# WIZARD_HV.net
KiCad netlist of a schematic drawn in Altium Designer
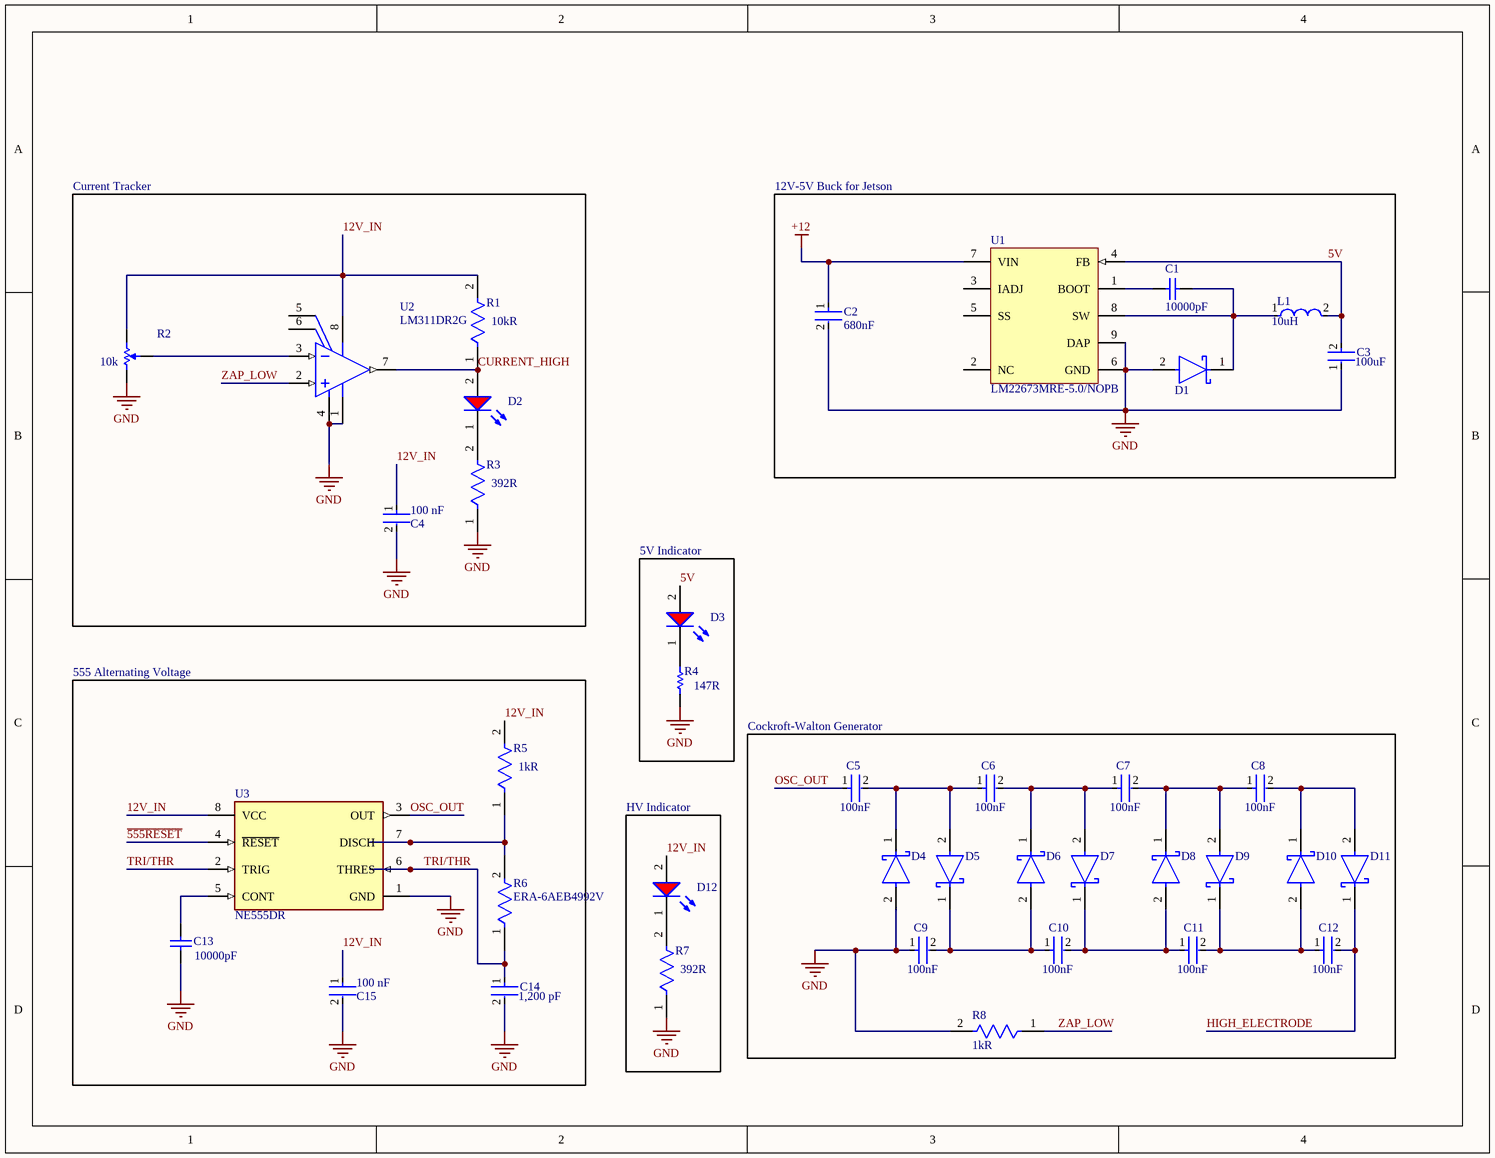
[diagram p0: WIZARD_HV.SchDoc]

(export (version "E")
  (design (tool "Eeschema 10.0.6"))
  (components
    (comp (ref "C1")
      (value "CL21B103KBANNNC")
      (footprint "CAPC2013X75X45LL10T25")
      (description "Multilayer Ceramic Capacitor, 10 nF, 50 V, -55 to 125 degC, 2-Pin SMD, RoHS, Tape and Reel")
      (fields
        (field (name "CAPACITANCE") "10000pF")
        (field (name "MANUFACTURER") "Samsung Electro-Mechanics")
      )
      (libsource (lib "Altium Content Vault") (part "CAP-NP-2"))
    )
    (comp (ref "C2")
      (value "CGA4J3X7R1E684K125AB")
      (footprint "FP-CGA4J-MFG")
      (description "Cap Ceramic 680nF 25V X7R 10% Pad SMD 0805 +125°C Automotive T/R")
      (fields (field (name "CAPACITANCE") "680nF") (field (name "TOLERANCE") "10%"))
      (libsource (lib "Altium Content Vault") (part "b4654b650e69147ec39a6b967a45e02"))
    )
    (comp (ref "C3")
      (value "GRM31CR61A107MEA8L")
      (footprint "FP-GRM31C-0_3-e0_3_0_8-IPC_B")
      (description "Chip Multilayer Ceramic Capacitors for General Purpose, 1206, 100uF, X5R, 15%, 20%, 10V")
      (fields (field (name "PARAMETER 1") "100uF"))
      (libsource (lib "Altium Content Vault") (part "f23184f103b6ebe33a8c269c53dcba6"))
    )
    (comp (ref "C4")
      (value "CC0805KRX7R9BB104")
      (footprint "FP-CC0805-0_85-MFG")
      (description "CAP CER 0.1UF 50V X7R 0805")
      (fields
        (field (name "TOLERANCE") "0.1")
        (field (name "CAPACITANCE") "100 nF")
        (field (name "MANUFACTURER") "Yageo")
      )
      (libsource (lib "Altium Content Vault") (part "11868f565c42a9108669ba33697ecf6"))
    )
    (comp (ref "C5")
      (value "C2012X7T2E104K125AA")
      (footprint "FP-C2012-125-0_2-IPC_B")
      (description "Multilayer Ceramic Capacitors 100nF ±10% 250V X7T SMD 0805")
      (fields (field (name "TOLERANCE") "10%") (field (name "CAPACITANCE") "100nF"))
      (libsource (lib "Altium Content Vault") (part "b4654b650e69147ec39a6b967a45e02"))
    )
    (comp (ref "C6")
      (value "C2012X7T2E104K125AA")
      (footprint "FP-C2012-125-0_2-IPC_B")
      (description "Multilayer Ceramic Capacitors 100nF ±10% 250V X7T SMD 0805")
      (fields (field (name "TOLERANCE") "10%") (field (name "CAPACITANCE") "100nF"))
      (libsource (lib "Altium Content Vault") (part "b4654b650e69147ec39a6b967a45e02"))
    )
    (comp (ref "C7")
      (value "C2012X7T2E104K125AA")
      (footprint "FP-C2012-125-0_2-IPC_B")
      (description "Multilayer Ceramic Capacitors 100nF ±10% 250V X7T SMD 0805")
      (fields (field (name "TOLERANCE") "10%") (field (name "CAPACITANCE") "100nF"))
      (libsource (lib "Altium Content Vault") (part "b4654b650e69147ec39a6b967a45e02"))
    )
    (comp (ref "C8")
      (value "C2012X7T2E104K125AA")
      (footprint "FP-C2012-125-0_2-IPC_B")
      (description "Multilayer Ceramic Capacitors 100nF ±10% 250V X7T SMD 0805")
      (fields (field (name "TOLERANCE") "10%") (field (name "CAPACITANCE") "100nF"))
      (libsource (lib "Altium Content Vault") (part "b4654b650e69147ec39a6b967a45e02"))
    )
    (comp (ref "C9")
      (value "C2012X7T2E104K125AA")
      (footprint "FP-C2012-125-0_2-IPC_B")
      (description "Multilayer Ceramic Capacitors 100nF ±10% 250V X7T SMD 0805")
      (fields (field (name "TOLERANCE") "10%") (field (name "CAPACITANCE") "100nF"))
      (libsource (lib "Altium Content Vault") (part "b4654b650e69147ec39a6b967a45e02"))
    )
    (comp (ref "C10")
      (value "C2012X7T2E104K125AA")
      (footprint "FP-C2012-125-0_2-IPC_B")
      (description "Multilayer Ceramic Capacitors 100nF ±10% 250V X7T SMD 0805")
      (fields (field (name "TOLERANCE") "10%") (field (name "CAPACITANCE") "100nF"))
      (libsource (lib "Altium Content Vault") (part "b4654b650e69147ec39a6b967a45e02"))
    )
    (comp (ref "C11")
      (value "C2012X7T2E104K125AA")
      (footprint "FP-C2012-125-0_2-IPC_B")
      (description "Multilayer Ceramic Capacitors 100nF ±10% 250V X7T SMD 0805")
      (fields (field (name "TOLERANCE") "10%") (field (name "CAPACITANCE") "100nF"))
      (libsource (lib "Altium Content Vault") (part "b4654b650e69147ec39a6b967a45e02"))
    )
    (comp (ref "C12")
      (value "C2012X7T2E104K125AA")
      (footprint "FP-C2012-125-0_2-IPC_B")
      (description "Multilayer Ceramic Capacitors 100nF ±10% 250V X7T SMD 0805")
      (fields (field (name "TOLERANCE") "10%") (field (name "CAPACITANCE") "100nF"))
      (libsource (lib "Altium Content Vault") (part "b4654b650e69147ec39a6b967a45e02"))
    )
    (comp (ref "C13")
      (value "CL21B103KBANNNC")
      (footprint "CAPC2013X75X45LL10T25")
      (description "Multilayer Ceramic Capacitor, 10 nF, 50 V, -55 to 125 degC, 2-Pin SMD, RoHS, Tape and Reel")
      (fields
        (field (name "CAPACITANCE") "10000pF")
        (field (name "MANUFACTURER") "Samsung Electro-Mechanics")
      )
      (libsource (lib "Altium Content Vault") (part "CAP-NP-2"))
    )
    (comp (ref "C14")
      (value "C0805C122K5RACTU")
      (footprint "FP-C0805C-DN-MFG")
      (description "CAP CER 1200PF 50V 10% X7R 0805")
      (fields
        (field (name "TOLERANCE") "0.1")
        (field (name "OCTOPART") "https://octopart.com/c0805c122k5ractu-kemet-8370191")
        (field (name "CAPACITANCE") "1,200 pF")
      )
      (libsource (lib "Altium Content Vault") (part "b4654b650e69147ec39a6b967a45e02"))
    )
    (comp (ref "C15")
      (value "CC0805KRX7R9BB104")
      (footprint "FP-CC0805-0_85-MFG")
      (description "CAP CER 0.1UF 50V X7R 0805")
      (fields
        (field (name "TOLERANCE") "0.1")
        (field (name "CAPACITANCE") "100 nF")
        (field (name "MANUFACTURER") "Yageo")
      )
      (libsource (lib "Altium Content Vault") (part "11868f565c42a9108669ba33697ecf6"))
    )
    (comp (ref "D1")
      (value "SK520B")
      (footprint "FP-SMB-MFG")
      (description "SK520B Diode Schottky 200V 5A Smb")
      (libsource (lib "Altium Content Vault") (part "c1678fac7984e62e0809fbf79c06691"))
    )
    (comp (ref "D2")
      (value "150080RS75000")
      (footprint "WL-SMCW_0805_150080xx75000")
      (description "LED Uni-Color Red 630nm 2-Pin Chip 0805(2012Metric) T/R")
      (libsource (lib "Altium Content Vault") (part "LED_Red_2A-1K"))
    )
    (comp (ref "D3")
      (value "150080RS75000")
      (footprint "WL-SMCW_0805_150080xx75000")
      (description "LED Uni-Color Red 630nm 2-Pin Chip 0805(2012Metric) T/R")
      (libsource (lib "Altium Content Vault") (part "LED_Red_2A-1K"))
    )
    (comp (ref "D4")
      (value "SK520B")
      (footprint "FP-SMB-MFG")
      (description "SK520B Diode Schottky 200V 5A Smb")
      (libsource (lib "Altium Content Vault") (part "c1678fac7984e62e0809fbf79c06691"))
    )
    (comp (ref "D5")
      (value "SK520B")
      (footprint "FP-SMB-MFG")
      (description "SK520B Diode Schottky 200V 5A Smb")
      (libsource (lib "Altium Content Vault") (part "c1678fac7984e62e0809fbf79c06691"))
    )
    (comp (ref "D6")
      (value "SK520B")
      (footprint "FP-SMB-MFG")
      (description "SK520B Diode Schottky 200V 5A Smb")
      (libsource (lib "Altium Content Vault") (part "c1678fac7984e62e0809fbf79c06691"))
    )
    (comp (ref "D7")
      (value "SK520B")
      (footprint "FP-SMB-MFG")
      (description "SK520B Diode Schottky 200V 5A Smb")
      (libsource (lib "Altium Content Vault") (part "c1678fac7984e62e0809fbf79c06691"))
    )
    (comp (ref "D8")
      (value "SK520B")
      (footprint "FP-SMB-MFG")
      (description "SK520B Diode Schottky 200V 5A Smb")
      (libsource (lib "Altium Content Vault") (part "c1678fac7984e62e0809fbf79c06691"))
    )
    (comp (ref "D9")
      (value "SK520B")
      (footprint "FP-SMB-MFG")
      (description "SK520B Diode Schottky 200V 5A Smb")
      (libsource (lib "Altium Content Vault") (part "c1678fac7984e62e0809fbf79c06691"))
    )
    (comp (ref "D10")
      (value "SK520B")
      (footprint "FP-SMB-MFG")
      (description "SK520B Diode Schottky 200V 5A Smb")
      (libsource (lib "Altium Content Vault") (part "c1678fac7984e62e0809fbf79c06691"))
    )
    (comp (ref "D11")
      (value "SK520B")
      (footprint "FP-SMB-MFG")
      (description "SK520B Diode Schottky 200V 5A Smb")
      (libsource (lib "Altium Content Vault") (part "c1678fac7984e62e0809fbf79c06691"))
    )
    (comp (ref "D12")
      (value "150080RS75000")
      (footprint "WL-SMCW_0805_150080xx75000")
      (description "LED Uni-Color Red 630nm 2-Pin Chip 0805(2012Metric) T/R")
      (libsource (lib "Altium Content Vault") (part "LED_Red_2A-1K"))
    )
    (comp (ref "L1")
      (value "SRP1038A-100M")
      (footprint "FP-SRP1038A-100M-MFG")
      (description "FIXED IND 10UH 7.5A 30 MOHM SMD")
      (fields (field (name "TOLERANCE") "20%") (field (name "INDUCTANCE") "10uH"))
      (libsource (lib "Altium Content Vault") (part "725321dda6339637d4d059423bc1c3c"))
    )
    (comp (ref "R1")
      (value "RR1220P-103-D")
      (footprint "FP-RR1220-IPC_A")
      (description "10kΩ ±0.5% 0.1W 1/10W Chip Resistor 0805 (2012 Metric) Thin Film")
      (fields (field (name "RESISTANCE") "10kR") (field (name "TOLERANCE") "0.5%"))
      (libsource (lib "Altium Content Vault") (part "1029c3af85768c4190bb7ad29bc67b5"))
    )
    (comp (ref "R2")
      (value "P090S-14T20BR10K")
      (footprint "RES-POT-3")
      (fields
        (field (name "TOLERANCE") "±20%")
        (field (name "MANUFACTURER") "BI Technologies")
        (field (name "RESISTANCE (OHMS)") "10k")
      )
      (libsource (lib "Altium Content Vault") (part "RES-ADJ-3_A"))
    )
    (comp (ref "R3")
      (value "RMCF0805FT392R")
      (footprint "FP-RMCF0805-IPC_A")
      (description "392Ω ±1% 0.125W 0805 Thick Film Chip Resistor AEC-Q200 compliant")
      (fields (field (name "TOLERANCE") "1%") (field (name "RESISTANCE") "392R"))
      (libsource (lib "Altium Content Vault") (part "1029c3af85768c4190bb7ad29bc67b5"))
    )
    (comp (ref "R4")
      (value "147R")
      (footprint "RESC2013X60X35NL10T20")
      (fields (field (name "MANUFACTURER") "Yageo") (field (name "PART NUMBER") "RC0805FR-07147RL"))
      (libsource (lib "Altium Content Vault") (part "RES"))
    )
    (comp (ref "R5")
      (value "RR1220P-102-D")
      (footprint "FP-RR1220-IPC_A")
      (description "1kΩ ±0.5% 0.1W 1/10W Chip Resistor 0805 (2012 Metric) Thin Film")
      (fields (field (name "TOLERANCE") "0.5%") (field (name "RESISTANCE") "1kR"))
      (libsource (lib "Altium Content Vault") (part "1029c3af85768c4190bb7ad29bc67b5"))
    )
    (comp (ref "R6")
      (value "ERA-6AEB4992V")
      (footprint "FP-ERA6A_MFG")
      (description "Res Thin Film 0805 49.9K Ohm 0.1% 0.125W(1/8W) +/-25ppm/ßC SMD Automotive T/R")
      (fields (field (name "TOLERANCE") "0.1%"))
      (libsource (lib "Altium Content Vault") (part "ERA-6AEB4992V"))
    )
    (comp (ref "R7")
      (value "RMCF0805FT392R")
      (footprint "FP-RMCF0805-IPC_A")
      (description "392Ω ±1% 0.125W 0805 Thick Film Chip Resistor AEC-Q200 compliant")
      (fields (field (name "TOLERANCE") "1%") (field (name "RESISTANCE") "392R"))
      (libsource (lib "Altium Content Vault") (part "1029c3af85768c4190bb7ad29bc67b5"))
    )
    (comp (ref "R8")
      (value "RR1220P-102-D")
      (footprint "FP-RR1220-IPC_A")
      (description "1kΩ ±0.5% 0.1W 1/10W Chip Resistor 0805 (2012 Metric) Thin Film")
      (fields (field (name "TOLERANCE") "0.5%") (field (name "RESISTANCE") "1kR"))
      (libsource (lib "Altium Content Vault") (part "1029c3af85768c4190bb7ad29bc67b5"))
    )
    (comp (ref "U1")
      (value "LM22673MRE-5.0/NOPB")
      (footprint "MRA08B_L")
      (fields (field (name "MANUFACTURER") "National Semiconductor"))
      (libsource (lib "Altium Content Vault") (part "PM-REG-LM22673MR"))
    )
    (comp (ref "U2")
      (value "LM311DR2G")
      (footprint "ONSC-SOIC-8-751-07_V")
      (description "Single Comparator, 5 to 30 V, 0 to 70 degC, 8-Pin SOIC, Pb-Free, Tape and Reel")
      (fields (field (name "MANUFACTURER") "On Semiconductor"))
      (libsource (lib "Altium Content Vault") (part "ONSC-LM211_311-8"))
    )
    (comp (ref "U3")
      (value "NE555DR")
      (footprint "FP-D0008A-IPC_A")
      (description "IC OSC SGL TIMER 100KHZ 8-SOIC")
      (libsource (lib "Altium Content Vault") (part "a29bba90211dec1890110b94dad7d53"))
    )
  )
  (nets
    (net (code "1") (name "+12") (class "Default")
      (node (ref "C2") (pin "1") (pinfunction "1_1") (pintype "passive"))
      (node (ref "U1") (pin "7") (pinfunction "VIN_7") (pintype "power_in"))
    )
    (net (code "2") (name "/5V") (class "Default")
      (node (ref "C3") (pin "2") (pinfunction "2_2") (pintype "passive"))
      (node (ref "D3") (pin "2") (pinfunction "A_2") (pintype "passive"))
      (node (ref "L1") (pin "2") (pinfunction "2_2") (pintype "passive"))
      (node (ref "U1") (pin "4") (pinfunction "FB_4") (pintype "input"))
    )
    (net (code "3") (name "/12V_IN") (class "Default")
      (node (ref "C15") (pin "1") (pinfunction "1_1") (pintype "passive"))
      (node (ref "C4") (pin "1") (pinfunction "1_1") (pintype "passive"))
      (node (ref "D12") (pin "2") (pinfunction "A_2") (pintype "passive"))
      (node (ref "R1") (pin "2") (pinfunction "2_2") (pintype "passive"))
      (node (ref "R2") (pin "3") (pinfunction "3_3") (pintype "passive"))
      (node (ref "R5") (pin "2") (pinfunction "2_2") (pintype "passive"))
      (node (ref "U2") (pin "8") (pinfunction "VCC_8") (pintype "power_in"))
      (node (ref "U3") (pin "8") (pinfunction "VCC_8") (pintype "power_in"))
    )
    (net (code "4") (name "/CURRENT_HIGH") (class "Default")
      (node (ref "D2") (pin "2") (pinfunction "A_2") (pintype "passive"))
      (node (ref "R1") (pin "1") (pinfunction "1_1") (pintype "passive"))
      (node (ref "U2") (pin "7") (pinfunction "OUT_7") (pintype "output"))
    )
    (net (code "5") (name "/HIGH_ELECTRODE") (class "Default")
      (node (ref "C12") (pin "2") (pinfunction "2_2") (pintype "passive"))
      (node (ref "D11") (pin "1") (pinfunction "C_1") (pintype "passive"))
    )
    (net (code "6") (name "/OSC_OUT") (class "Default")
      (node (ref "C5") (pin "1") (pinfunction "1_1") (pintype "passive"))
      (node (ref "U3") (pin "3") (pinfunction "OUT_3") (pintype "output"))
    )
    (net (code "7") (name "/TRI{slash}THR") (class "Default")
      (node (ref "C14") (pin "1") (pinfunction "1_1") (pintype "passive"))
      (node (ref "R6") (pin "1") (pinfunction "1_1") (pintype "passive"))
      (node (ref "U3") (pin "2") (pinfunction "TRIG_2") (pintype "input"))
      (node (ref "U3") (pin "6") (pinfunction "THRES_6") (pintype "input"))
    )
    (net (code "8") (name "/ZAP_LOW") (class "Default")
      (node (ref "R8") (pin "1") (pinfunction "1_1") (pintype "passive"))
      (node (ref "U2") (pin "2") (pinfunction "IN+_2") (pintype "input"))
    )
    (net (code "9") (name "/~{555RESET}") (class "Default")
      (node (ref "U3") (pin "4") (pinfunction "~{RESET}_4") (pintype "input"))
    )
    (net (code "10") (name "GND") (class "Default")
      (node (ref "C13") (pin "1") (pinfunction "1_1") (pintype "passive"))
      (node (ref "C14") (pin "2") (pinfunction "2_2") (pintype "passive"))
      (node (ref "C15") (pin "2") (pinfunction "2_2") (pintype "passive"))
      (node (ref "C2") (pin "2") (pinfunction "2_2") (pintype "passive"))
      (node (ref "C3") (pin "1") (pinfunction "1_1") (pintype "passive"))
      (node (ref "C4") (pin "2") (pinfunction "2_2") (pintype "passive"))
      (node (ref "C9") (pin "1") (pinfunction "1_1") (pintype "passive"))
      (node (ref "D1") (pin "2") (pinfunction "A_2") (pintype "passive"))
      (node (ref "D4") (pin "2") (pinfunction "A_2") (pintype "passive"))
      (node (ref "R2") (pin "1") (pinfunction "1_1") (pintype "passive"))
      (node (ref "R3") (pin "1") (pinfunction "1_1") (pintype "passive"))
      (node (ref "R4") (pin "1") (pinfunction "1_1") (pintype "passive"))
      (node (ref "R7") (pin "1") (pinfunction "1_1") (pintype "passive"))
      (node (ref "R8") (pin "2") (pinfunction "2_2") (pintype "passive"))
      (node (ref "U1") (pin "6") (pinfunction "GND_6") (pintype "power_in"))
      (node (ref "U1") (pin "9") (pinfunction "DAP_9") (pintype "power_in"))
      (node (ref "U2") (pin "1") (pinfunction "GND_1") (pintype "power_in"))
      (node (ref "U2") (pin "4") (pinfunction "VEE_4") (pintype "power_in"))
      (node (ref "U3") (pin "1") (pinfunction "GND_1") (pintype "power_in"))
    )
    (net (code "11") (name "Net-(D1-C)") (class "Default")
      (node (ref "C1") (pin "1") (pinfunction "1_1") (pintype "passive"))
      (node (ref "D1") (pin "1") (pinfunction "C_1") (pintype "passive"))
      (node (ref "L1") (pin "1") (pinfunction "1_1") (pintype "passive"))
      (node (ref "U1") (pin "8") (pinfunction "SW_8") (pintype "power_in"))
    )
    (net (code "12") (name "Net-(D2-K)") (class "Default")
      (node (ref "D2") (pin "1") (pinfunction "K_1") (pintype "passive"))
      (node (ref "R3") (pin "2") (pinfunction "2_2") (pintype "passive"))
    )
    (net (code "13") (name "Net-(D3-K)") (class "Default")
      (node (ref "D3") (pin "1") (pinfunction "K_1") (pintype "passive"))
      (node (ref "R4") (pin "2") (pinfunction "2_2") (pintype "passive"))
    )
    (net (code "14") (name "Net-(D4-C)") (class "Default")
      (node (ref "C5") (pin "2") (pinfunction "2_2") (pintype "passive"))
      (node (ref "C6") (pin "1") (pinfunction "1_1") (pintype "passive"))
      (node (ref "D4") (pin "1") (pinfunction "C_1") (pintype "passive"))
      (node (ref "D5") (pin "2") (pinfunction "A_2") (pintype "passive"))
    )
    (net (code "15") (name "Net-(D5-C)") (class "Default")
      (node (ref "C10") (pin "1") (pinfunction "1_1") (pintype "passive"))
      (node (ref "C9") (pin "2") (pinfunction "2_2") (pintype "passive"))
      (node (ref "D5") (pin "1") (pinfunction "C_1") (pintype "passive"))
      (node (ref "D6") (pin "2") (pinfunction "A_2") (pintype "passive"))
    )
    (net (code "16") (name "Net-(D6-C)") (class "Default")
      (node (ref "C6") (pin "2") (pinfunction "2_2") (pintype "passive"))
      (node (ref "C7") (pin "1") (pinfunction "1_1") (pintype "passive"))
      (node (ref "D6") (pin "1") (pinfunction "C_1") (pintype "passive"))
      (node (ref "D7") (pin "2") (pinfunction "A_2") (pintype "passive"))
    )
    (net (code "17") (name "Net-(D7-C)") (class "Default")
      (node (ref "C10") (pin "2") (pinfunction "2_2") (pintype "passive"))
      (node (ref "C11") (pin "1") (pinfunction "1_1") (pintype "passive"))
      (node (ref "D7") (pin "1") (pinfunction "C_1") (pintype "passive"))
      (node (ref "D8") (pin "2") (pinfunction "A_2") (pintype "passive"))
    )
    (net (code "18") (name "Net-(D8-C)") (class "Default")
      (node (ref "C7") (pin "2") (pinfunction "2_2") (pintype "passive"))
      (node (ref "C8") (pin "1") (pinfunction "1_1") (pintype "passive"))
      (node (ref "D8") (pin "1") (pinfunction "C_1") (pintype "passive"))
      (node (ref "D9") (pin "2") (pinfunction "A_2") (pintype "passive"))
    )
    (net (code "19") (name "Net-(D10-A)") (class "Default")
      (node (ref "C11") (pin "2") (pinfunction "2_2") (pintype "passive"))
      (node (ref "C12") (pin "1") (pinfunction "1_1") (pintype "passive"))
      (node (ref "D10") (pin "2") (pinfunction "A_2") (pintype "passive"))
      (node (ref "D9") (pin "1") (pinfunction "C_1") (pintype "passive"))
    )
    (net (code "20") (name "Net-(D10-C)") (class "Default")
      (node (ref "C8") (pin "2") (pinfunction "2_2") (pintype "passive"))
      (node (ref "D10") (pin "1") (pinfunction "C_1") (pintype "passive"))
      (node (ref "D11") (pin "2") (pinfunction "A_2") (pintype "passive"))
    )
    (net (code "21") (name "Net-(D12-K)") (class "Default")
      (node (ref "D12") (pin "1") (pinfunction "K_1") (pintype "passive"))
      (node (ref "R7") (pin "2") (pinfunction "2_2") (pintype "passive"))
    )
    (net (code "22") (name "Net-(U1-BOOT)") (class "Default")
      (node (ref "C1") (pin "2") (pinfunction "2_2") (pintype "passive"))
      (node (ref "U1") (pin "1") (pinfunction "BOOT_1") (pintype "passive"))
    )
    (net (code "23") (name "Net-(U2-IN-)") (class "Default")
      (node (ref "R2") (pin "2") (pinfunction "2_2") (pintype "passive"))
      (node (ref "U2") (pin "3") (pinfunction "IN-_3") (pintype "input"))
    )
    (net (code "24") (name "Net-(U3-CONT)") (class "Default")
      (node (ref "C13") (pin "2") (pinfunction "2_2") (pintype "passive"))
      (node (ref "U3") (pin "5") (pinfunction "CONT_5") (pintype "input"))
    )
    (net (code "25") (name "Net-(U3-DISCH)") (class "Default")
      (node (ref "R5") (pin "1") (pinfunction "1_1") (pintype "passive"))
      (node (ref "R6") (pin "2") (pinfunction "2_2") (pintype "passive"))
      (node (ref "U3") (pin "7") (pinfunction "DISCH_7") (pintype "open_collector"))
    )
    (net (code "26") (name "unconnected-(U1-IADJ-Pad3)") (class "Default")
      (node (ref "U1") (pin "3") (pinfunction "IADJ_3") (pintype "passive"))
    )
    (net (code "27") (name "unconnected-(U1-NC-Pad2)") (class "Default")
      (node (ref "U1") (pin "2") (pinfunction "NC_2") (pintype "passive"))
    )
    (net (code "28") (name "unconnected-(U1-SS-Pad5)") (class "Default")
      (node (ref "U1") (pin "5") (pinfunction "SS_5") (pintype "passive"))
    )
    (net (code "29") (name "unconnected-(U2-BALANCE-Pad5)") (class "Default")
      (node (ref "U2") (pin "5") (pinfunction "BALANCE_5") (pintype "passive"))
    )
    (net (code "30") (name "unconnected-(U2-BALANCE{slash}STROBE-Pad6)") (class "Default")
      (node (ref "U2") (pin "6") (pinfunction "BALANCE/STROBE_6") (pintype "passive"))
    )
  )
)
